# mySensorsRS485GW_front_v2.net
KiCad netlist of a schematic drawn in EAGLE
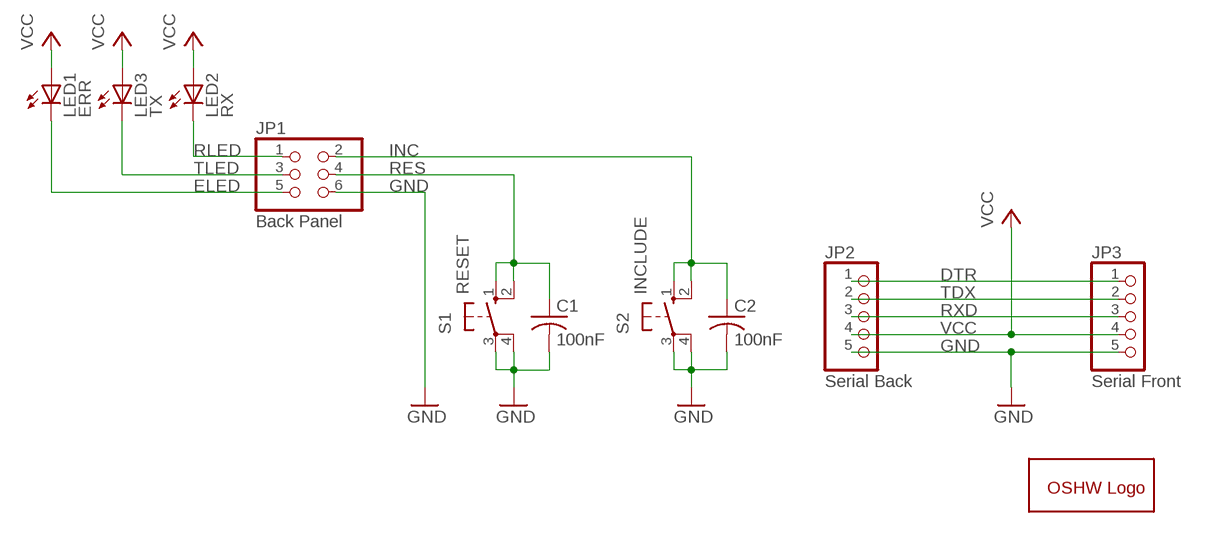
[diagram p0: schematic, sheet 1]

(export (version "E")
  (design (tool "Eeschema 10.0.6"))
  (components
    (comp (ref "C1")
      (value "100nF")
      (footprint "eagle-import:C025-025X050")
      (libsource (lib "eagle-import") (part "C-US025-025X050"))
    )
    (comp (ref "C2")
      (value "100nF")
      (footprint "eagle-import:C025-025X050")
      (libsource (lib "eagle-import") (part "C-US025-025X050"))
    )
    (comp (ref "GOLD_ORB_SM1")
      (value "OSHWLOGOLOGO5MM")
      (footprint "eagle-import:OSHW_5MM")
      (libsource (lib "eagle-import") (part "OSHWLOGOLOGO5MM"))
    )
    (comp (ref "JP1")
      (value "Back Panel")
      (footprint "eagle-import:2X03")
      (libsource (lib "eagle-import") (part "PINHD-2X3"))
    )
    (comp (ref "JP2")
      (value "Serial Back")
      (footprint "eagle-import:1X05")
      (libsource (lib "eagle-import") (part "PINHD-1X5"))
    )
    (comp (ref "JP3")
      (value "Serial Front")
      (footprint "eagle-import:1X05")
      (libsource (lib "eagle-import") (part "PINHD-1X5"))
    )
    (comp (ref "LED1")
      (value "ERR")
      (footprint "eagle-import:LED3MM")
      (libsource (lib "eagle-import") (part "LED3MM"))
    )
    (comp (ref "LED2")
      (value "RX")
      (footprint "eagle-import:LED3MM")
      (libsource (lib "eagle-import") (part "LED3MM"))
    )
    (comp (ref "LED3")
      (value "TX")
      (footprint "eagle-import:LED3MM")
      (libsource (lib "eagle-import") (part "LED3MM"))
    )
    (comp (ref "S1")
      (value "RESET")
      (footprint "eagle-import:B3F-10XX")
      (fields (field (name "MPN") "B3F-1000"))
      (libsource (lib "eagle-import") (part "10-XX"))
    )
    (comp (ref "S2")
      (value "INCLUDE")
      (footprint "eagle-import:B3F-10XX")
      (fields (field (name "MPN") "B3F-1000"))
      (libsource (lib "eagle-import") (part "10-XX"))
    )
  )
  (nets
    (net (code "1") (name "/DTR") (class "Default")
      (node (ref "JP2") (pin "1") (pinfunction "1_1") (pintype "passive"))
      (node (ref "JP3") (pin "1") (pinfunction "1_1") (pintype "passive"))
    )
    (net (code "2") (name "/ELED") (class "Default")
      (node (ref "JP1") (pin "5") (pinfunction "5_5") (pintype "passive"))
      (node (ref "LED1") (pin "K") (pinfunction "C_K") (pintype "passive"))
    )
    (net (code "3") (name "/INC") (class "Default")
      (node (ref "C2") (pin "1") (pinfunction "1_1") (pintype "passive"))
      (node (ref "JP1") (pin "2") (pinfunction "2_2") (pintype "passive"))
      (node (ref "S2") (pin "1") (pinfunction "S_1") (pintype "passive"))
      (node (ref "S2") (pin "2") (pinfunction "S1_2") (pintype "passive"))
    )
    (net (code "4") (name "/RES") (class "Default")
      (node (ref "C1") (pin "1") (pinfunction "1_1") (pintype "passive"))
      (node (ref "JP1") (pin "4") (pinfunction "4_4") (pintype "passive"))
      (node (ref "S1") (pin "1") (pinfunction "S_1") (pintype "passive"))
      (node (ref "S1") (pin "2") (pinfunction "S1_2") (pintype "passive"))
    )
    (net (code "5") (name "/RLED") (class "Default")
      (node (ref "JP1") (pin "1") (pinfunction "1_1") (pintype "passive"))
      (node (ref "LED2") (pin "K") (pinfunction "C_K") (pintype "passive"))
    )
    (net (code "6") (name "/RXD") (class "Default")
      (node (ref "JP2") (pin "3") (pinfunction "3_3") (pintype "passive"))
      (node (ref "JP3") (pin "3") (pinfunction "3_3") (pintype "passive"))
    )
    (net (code "7") (name "/TDX") (class "Default")
      (node (ref "JP2") (pin "2") (pinfunction "2_2") (pintype "passive"))
      (node (ref "JP3") (pin "2") (pinfunction "2_2") (pintype "passive"))
    )
    (net (code "8") (name "/TLED") (class "Default")
      (node (ref "JP1") (pin "3") (pinfunction "3_3") (pintype "passive"))
      (node (ref "LED3") (pin "K") (pinfunction "C_K") (pintype "passive"))
    )
    (net (code "9") (name "GND") (class "Default")
      (node (ref "C1") (pin "2") (pinfunction "2_2") (pintype "passive"))
      (node (ref "C2") (pin "2") (pinfunction "2_2") (pintype "passive"))
      (node (ref "JP1") (pin "6") (pinfunction "6_6") (pintype "passive"))
      (node (ref "JP2") (pin "5") (pinfunction "5_5") (pintype "passive"))
      (node (ref "JP3") (pin "5") (pinfunction "5_5") (pintype "passive"))
      (node (ref "S1") (pin "3") (pinfunction "P_3") (pintype "passive"))
      (node (ref "S1") (pin "4") (pinfunction "P1_4") (pintype "passive"))
      (node (ref "S2") (pin "3") (pinfunction "P_3") (pintype "passive"))
      (node (ref "S2") (pin "4") (pinfunction "P1_4") (pintype "passive"))
    )
    (net (code "10") (name "VCC") (class "Default")
      (node (ref "JP2") (pin "4") (pinfunction "4_4") (pintype "passive"))
      (node (ref "JP3") (pin "4") (pinfunction "4_4") (pintype "passive"))
      (node (ref "LED1") (pin "A") (pinfunction "A_A") (pintype "passive"))
      (node (ref "LED2") (pin "A") (pinfunction "A_A") (pintype "passive"))
      (node (ref "LED3") (pin "A") (pinfunction "A_A") (pintype "passive"))
    )
  )
)
